# MainPage.net
KiCad netlist of a schematic drawn in Altium Designer
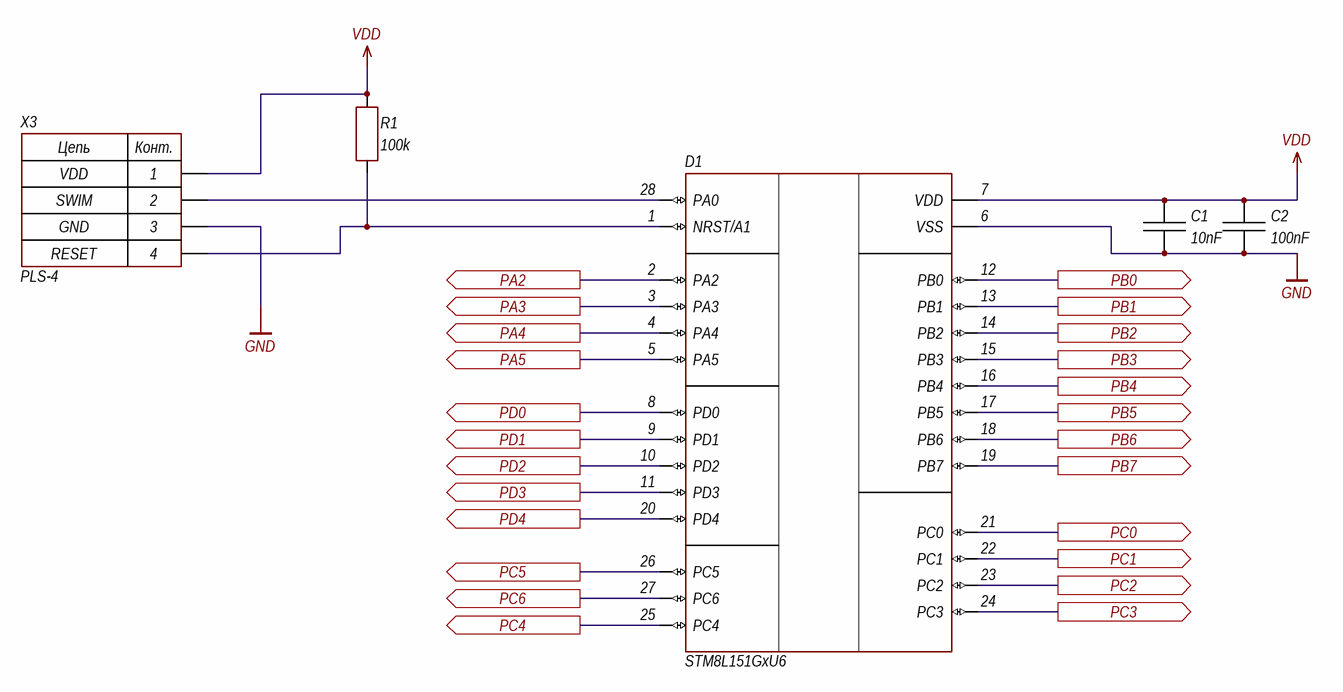
[diagram p0: MainPage.SchDoc]

(export (version "E")
  (design (tool "Eeschema 10.0.6"))
  (components
    (comp (ref "C1") (value "10nF") (footprint "CH0402C") (libsource (lib "Discrete") (part "Capacitor")))
    (comp (ref "C2") (value "100nF") (footprint "CH0402C") (libsource (lib "Discrete") (part "Capacitor")))
    (comp (ref "D1")
      (value "STM8L151GxU6")
      (footprint "28-UFQFPN")
      (description "STM8")
      (fields (field (name "MANUFACTURER") "ST Microelectronics"))
      (libsource (lib "Digital") (part "STM8L151GxU6"))
    )
    (comp (ref "R1") (value "100k") (footprint "CH0402R") (libsource (lib "Discrete") (part "Resistor")))
    (comp (ref "X3")
      (value "PLS-4")
      (footprint "CON: PLS-4")
      (libsource (lib "Connectors") (part "4-Connector"))
    )
  )
  (nets
    (net (code "1") (name "/PA2") (class "Default")
      (node (ref "D1") (pin "2") (pinfunction "PA2_2") (pintype "bidirectional"))
    )
    (net (code "2") (name "/PA3") (class "Default")
      (node (ref "D1") (pin "3") (pinfunction "PA3_3") (pintype "bidirectional"))
    )
    (net (code "3") (name "/PA4") (class "Default")
      (node (ref "D1") (pin "4") (pinfunction "PA4_4") (pintype "bidirectional"))
    )
    (net (code "4") (name "/PA5") (class "Default")
      (node (ref "D1") (pin "5") (pinfunction "PA5_5") (pintype "bidirectional"))
    )
    (net (code "5") (name "/PB0") (class "Default")
      (node (ref "D1") (pin "12") (pinfunction "PB0_12") (pintype "bidirectional"))
    )
    (net (code "6") (name "/PB1") (class "Default")
      (node (ref "D1") (pin "13") (pinfunction "PB1_13") (pintype "bidirectional"))
    )
    (net (code "7") (name "/PB2") (class "Default")
      (node (ref "D1") (pin "14") (pinfunction "PB2_14") (pintype "bidirectional"))
    )
    (net (code "8") (name "/PB3") (class "Default")
      (node (ref "D1") (pin "15") (pinfunction "PB3_15") (pintype "bidirectional"))
    )
    (net (code "9") (name "/PB4") (class "Default")
      (node (ref "D1") (pin "16") (pinfunction "PB4_16") (pintype "bidirectional"))
    )
    (net (code "10") (name "/PB5") (class "Default")
      (node (ref "D1") (pin "17") (pinfunction "PB5_17") (pintype "bidirectional"))
    )
    (net (code "11") (name "/PB6") (class "Default")
      (node (ref "D1") (pin "18") (pinfunction "PB6_18") (pintype "bidirectional"))
    )
    (net (code "12") (name "/PB7") (class "Default")
      (node (ref "D1") (pin "19") (pinfunction "PB7_19") (pintype "bidirectional"))
    )
    (net (code "13") (name "/PC0") (class "Default")
      (node (ref "D1") (pin "21") (pinfunction "PC0_21") (pintype "bidirectional"))
    )
    (net (code "14") (name "/PC1") (class "Default")
      (node (ref "D1") (pin "22") (pinfunction "PC1_22") (pintype "bidirectional"))
    )
    (net (code "15") (name "/PC2") (class "Default")
      (node (ref "D1") (pin "23") (pinfunction "PC2_23") (pintype "bidirectional"))
    )
    (net (code "16") (name "/PC3") (class "Default")
      (node (ref "D1") (pin "24") (pinfunction "PC3_24") (pintype "bidirectional"))
    )
    (net (code "17") (name "/PC4") (class "Default")
      (node (ref "D1") (pin "25") (pinfunction "PC4_25") (pintype "bidirectional"))
    )
    (net (code "18") (name "/PC5") (class "Default")
      (node (ref "D1") (pin "26") (pinfunction "PC5_26") (pintype "bidirectional"))
    )
    (net (code "19") (name "/PC6") (class "Default")
      (node (ref "D1") (pin "27") (pinfunction "PC6_27") (pintype "bidirectional"))
    )
    (net (code "20") (name "/PD0") (class "Default")
      (node (ref "D1") (pin "8") (pinfunction "PD0_8") (pintype "bidirectional"))
    )
    (net (code "21") (name "/PD1") (class "Default")
      (node (ref "D1") (pin "9") (pinfunction "PD1_9") (pintype "bidirectional"))
    )
    (net (code "22") (name "/PD2") (class "Default")
      (node (ref "D1") (pin "10") (pinfunction "PD2_10") (pintype "bidirectional"))
    )
    (net (code "23") (name "/PD3") (class "Default")
      (node (ref "D1") (pin "11") (pinfunction "PD3_11") (pintype "bidirectional"))
    )
    (net (code "24") (name "/PD4") (class "Default")
      (node (ref "D1") (pin "20") (pinfunction "PD4_20") (pintype "bidirectional"))
    )
    (net (code "25") (name "GND") (class "Default")
      (node (ref "C1") (pin "1") (pinfunction "1_1") (pintype "passive"))
      (node (ref "C2") (pin "1") (pinfunction "1_1") (pintype "passive"))
      (node (ref "D1") (pin "6") (pinfunction "VSS_6") (pintype "power_in"))
      (node (ref "X3") (pin "3") (pinfunction "3_3") (pintype "passive"))
    )
    (net (code "26") (name "Net-(D1-NRST{slash}A1)") (class "Default")
      (node (ref "D1") (pin "1") (pinfunction "NRST/A1_1") (pintype "bidirectional"))
      (node (ref "R1") (pin "1") (pinfunction "1_1") (pintype "passive"))
      (node (ref "X3") (pin "4") (pinfunction "4_4") (pintype "passive"))
    )
    (net (code "27") (name "Net-(D1-PA0)") (class "Default")
      (node (ref "D1") (pin "28") (pinfunction "PA0_28") (pintype "bidirectional"))
      (node (ref "X3") (pin "2") (pinfunction "2_2") (pintype "passive"))
    )
    (net (code "28") (name "VDD") (class "Default")
      (node (ref "C1") (pin "2") (pinfunction "2_2") (pintype "passive"))
      (node (ref "C2") (pin "2") (pinfunction "2_2") (pintype "passive"))
      (node (ref "D1") (pin "7") (pinfunction "VDD_7") (pintype "power_in"))
      (node (ref "R1") (pin "2") (pinfunction "2_2") (pintype "passive"))
      (node (ref "X3") (pin "1") (pinfunction "1_1") (pintype "passive"))
    )
  )
)
